# PCB_RX.net
KiCad netlist of a schematic drawn in Altium Designer
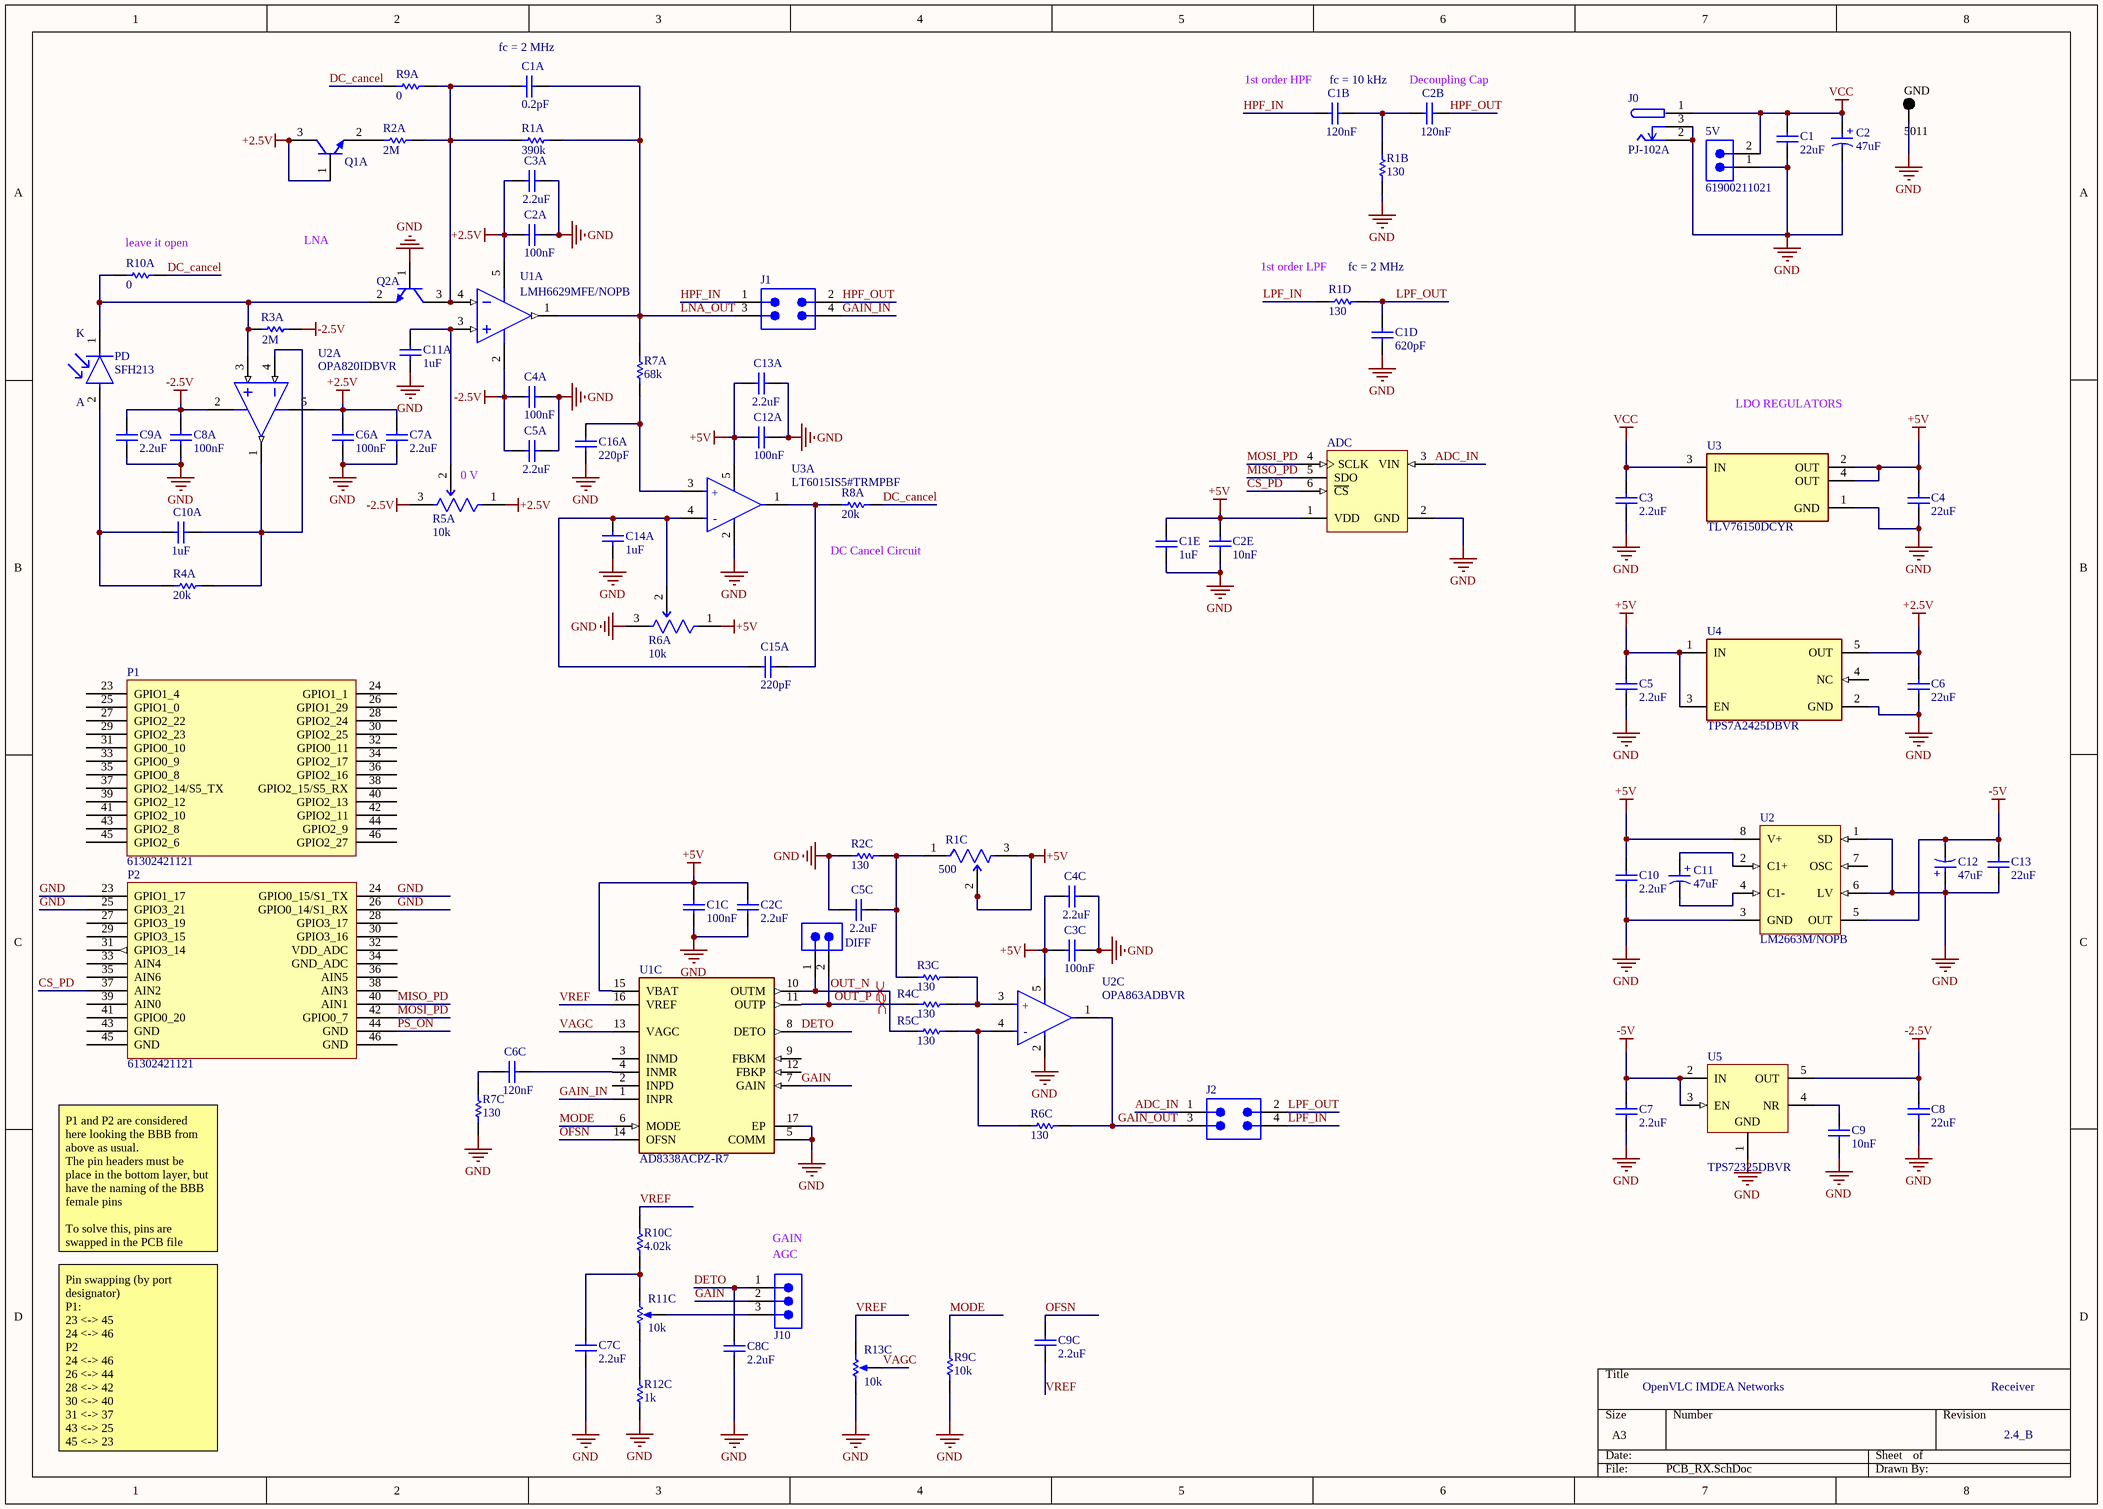
[diagram p0: PCB_RX.SchDoc]

(export (version "E")
  (design (tool "Eeschema 10.0.6"))
  (components
    (comp (ref "5V")
      (value "61900211021")
      (footprint "61900211021")
      (libsource (lib "Altium Content Vault") (part "Header_Male_1R_02P"))
    )
    (comp (ref "ADC")
      (value "ADS7886SBDBVR")
      (footprint "TI-DBV6_M")
      (fields (field (name "MANUFACTURER") "Texas Instruments"))
      (libsource (lib "Altium Content Vault") (part "TI-ADS788XDXX6"))
    )
    (comp (ref "C1")
      (value "22uF")
      (footprint "RESC1608X55N")
      (description "Capacitor")
      (fields (field (name "Comment") "Cap") (field (name "PUBLISHER") "Altium Limited"))
      (libsource (lib "Miscellaneous Devices") (part "Cap"))
    )
    (comp (ref "C1A")
      (value "0.2pF")
      (footprint "RESC1608X55N")
      (description "Capacitor")
      (fields (field (name "Comment") "Cap") (field (name "PUBLISHER") "Altium Limited"))
      (libsource (lib "Miscellaneous Devices") (part "Cap"))
    )
    (comp (ref "C1B")
      (value "120nF")
      (footprint "RESC1608X55N")
      (description "Capacitor")
      (fields (field (name "Comment") "Cap") (field (name "PUBLISHER") "Altium Limited"))
      (libsource (lib "Miscellaneous Devices") (part "Cap"))
    )
    (comp (ref "C1C")
      (value "100nF")
      (footprint "RESC1608X55N")
      (description "Capacitor")
      (fields (field (name "Comment") "Cap") (field (name "PUBLISHER") "Altium Limited"))
      (libsource (lib "Miscellaneous Devices") (part "Cap"))
    )
    (comp (ref "C1D")
      (value "620pF")
      (footprint "RESC1608X55N")
      (description "Capacitor")
      (fields (field (name "Comment") "Cap") (field (name "PUBLISHER") "Altium Limited"))
      (libsource (lib "Miscellaneous Devices") (part "Cap"))
    )
    (comp (ref "C1E")
      (value "1uF")
      (footprint "RESC1608X55N")
      (description "Capacitor")
      (fields (field (name "Comment") "Cap") (field (name "PUBLISHER") "Altium Limited"))
      (libsource (lib "Miscellaneous Devices") (part "Cap"))
    )
    (comp (ref "C2")
      (value "47uF")
      (footprint "WCAP-PSLP_D5H5.5")
      (description "875105242006 WCAP-PSLP Aluminum Polymer Capacitors")
      (fields (field (name "TOLERANCE") "20%"))
      (libsource (lib "Altium Content Vault") (part "Capacitor_Polarized"))
    )
    (comp (ref "C2A")
      (value "100nF")
      (footprint "RESC1608X55N")
      (description "Capacitor")
      (fields (field (name "Comment") "Cap") (field (name "PUBLISHER") "Altium Limited"))
      (libsource (lib "Miscellaneous Devices") (part "Cap"))
    )
    (comp (ref "C2B")
      (value "120nF")
      (footprint "RESC1608X55N")
      (description "Capacitor")
      (fields (field (name "Comment") "Cap") (field (name "PUBLISHER") "Altium Limited"))
      (libsource (lib "Miscellaneous Devices") (part "Cap"))
    )
    (comp (ref "C2C")
      (value "2.2uF")
      (footprint "RESC1608X55N")
      (description "Capacitor")
      (fields (field (name "Comment") "Cap") (field (name "PUBLISHER") "Altium Limited"))
      (libsource (lib "Miscellaneous Devices") (part "Cap"))
    )
    (comp (ref "C2E")
      (value "10nF")
      (footprint "RESC1608X55N")
      (description "Capacitor")
      (fields (field (name "Comment") "Cap") (field (name "PUBLISHER") "Altium Limited"))
      (libsource (lib "Miscellaneous Devices") (part "Cap"))
    )
    (comp (ref "C3")
      (value "2.2uF")
      (footprint "RESC1608X55N")
      (description "Capacitor")
      (fields (field (name "Comment") "Cap") (field (name "PUBLISHER") "Altium Limited"))
      (libsource (lib "Miscellaneous Devices") (part "Cap"))
    )
    (comp (ref "C3A")
      (value "2.2uF")
      (footprint "RESC1608X55N")
      (description "Capacitor")
      (fields (field (name "Comment") "Cap") (field (name "PUBLISHER") "Altium Limited"))
      (libsource (lib "Miscellaneous Devices") (part "Cap"))
    )
    (comp (ref "C3C")
      (value "100nF")
      (footprint "RESC1608X55N")
      (description "Capacitor")
      (fields (field (name "Comment") "Cap") (field (name "PUBLISHER") "Altium Limited"))
      (libsource (lib "Miscellaneous Devices") (part "Cap"))
    )
    (comp (ref "C4")
      (value "22uF")
      (footprint "RESC1608X55N")
      (description "Capacitor")
      (fields (field (name "Comment") "Cap") (field (name "PUBLISHER") "Altium Limited"))
      (libsource (lib "Miscellaneous Devices") (part "Cap"))
    )
    (comp (ref "C4A")
      (value "100nF")
      (footprint "RESC1608X55N")
      (description "Capacitor")
      (fields (field (name "Comment") "Cap") (field (name "PUBLISHER") "Altium Limited"))
      (libsource (lib "Miscellaneous Devices") (part "Cap"))
    )
    (comp (ref "C4C")
      (value "2.2uF")
      (footprint "RESC1608X55N")
      (description "Capacitor")
      (fields (field (name "Comment") "Cap") (field (name "PUBLISHER") "Altium Limited"))
      (libsource (lib "Miscellaneous Devices") (part "Cap"))
    )
    (comp (ref "C5")
      (value "2.2uF")
      (footprint "RESC1608X55N")
      (description "Capacitor")
      (fields (field (name "Comment") "Cap") (field (name "PUBLISHER") "Altium Limited"))
      (libsource (lib "Miscellaneous Devices") (part "Cap"))
    )
    (comp (ref "C5A")
      (value "2.2uF")
      (footprint "RESC1608X55N")
      (description "Capacitor")
      (fields (field (name "Comment") "Cap") (field (name "PUBLISHER") "Altium Limited"))
      (libsource (lib "Miscellaneous Devices") (part "Cap"))
    )
    (comp (ref "C5C")
      (value "2.2uF")
      (footprint "RESC1608X55N")
      (description "Capacitor")
      (fields (field (name "Comment") "Cap") (field (name "PUBLISHER") "Altium Limited"))
      (libsource (lib "Miscellaneous Devices") (part "Cap"))
    )
    (comp (ref "C6")
      (value "22uF")
      (footprint "RESC1608X55N")
      (description "Capacitor")
      (fields (field (name "Comment") "Cap") (field (name "PUBLISHER") "Altium Limited"))
      (libsource (lib "Miscellaneous Devices") (part "Cap"))
    )
    (comp (ref "C6A")
      (value "100nF")
      (footprint "RESC1608X55N")
      (description "Capacitor")
      (fields (field (name "Comment") "Cap") (field (name "PUBLISHER") "Altium Limited"))
      (libsource (lib "Miscellaneous Devices") (part "Cap"))
    )
    (comp (ref "C6C")
      (value "120nF")
      (footprint "RESC1608X55N")
      (description "Capacitor")
      (fields (field (name "Comment") "Cap") (field (name "PUBLISHER") "Altium Limited"))
      (libsource (lib "Miscellaneous Devices") (part "Cap"))
    )
    (comp (ref "C7")
      (value "2.2uF")
      (footprint "RESC1608X55N")
      (description "Capacitor")
      (fields (field (name "Comment") "Cap") (field (name "PUBLISHER") "Altium Limited"))
      (libsource (lib "Miscellaneous Devices") (part "Cap"))
    )
    (comp (ref "C7A")
      (value "2.2uF")
      (footprint "RESC1608X55N")
      (description "Capacitor")
      (fields (field (name "Comment") "Cap") (field (name "PUBLISHER") "Altium Limited"))
      (libsource (lib "Miscellaneous Devices") (part "Cap"))
    )
    (comp (ref "C7C")
      (value "2.2uF")
      (footprint "RESC1608X55N")
      (description "Capacitor")
      (fields (field (name "Comment") "Cap") (field (name "PUBLISHER") "Altium Limited"))
      (libsource (lib "Miscellaneous Devices") (part "Cap"))
    )
    (comp (ref "C8")
      (value "22uF")
      (footprint "RESC1608X55N")
      (description "Capacitor")
      (fields (field (name "Comment") "Cap") (field (name "PUBLISHER") "Altium Limited"))
      (libsource (lib "Miscellaneous Devices") (part "Cap"))
    )
    (comp (ref "C8A")
      (value "100nF")
      (footprint "RESC1608X55N")
      (description "Capacitor")
      (fields (field (name "Comment") "Cap") (field (name "PUBLISHER") "Altium Limited"))
      (libsource (lib "Miscellaneous Devices") (part "Cap"))
    )
    (comp (ref "C8C")
      (value "2.2uF")
      (footprint "RESC1608X55N")
      (description "Capacitor")
      (fields (field (name "Comment") "Cap") (field (name "PUBLISHER") "Altium Limited"))
      (libsource (lib "Miscellaneous Devices") (part "Cap"))
    )
    (comp (ref "C9")
      (value "10nF")
      (footprint "RESC1608X55N")
      (description "Capacitor")
      (fields (field (name "Comment") "Cap") (field (name "PUBLISHER") "Altium Limited"))
      (libsource (lib "Miscellaneous Devices") (part "Cap"))
    )
    (comp (ref "C9A")
      (value "2.2uF")
      (footprint "RESC1608X55N")
      (description "Capacitor")
      (fields (field (name "Comment") "Cap") (field (name "PUBLISHER") "Altium Limited"))
      (libsource (lib "Miscellaneous Devices") (part "Cap"))
    )
    (comp (ref "C9C")
      (value "2.2uF")
      (footprint "RESC1608X55N")
      (description "Capacitor")
      (fields (field (name "Comment") "Cap") (field (name "PUBLISHER") "Altium Limited"))
      (libsource (lib "Miscellaneous Devices") (part "Cap"))
    )
    (comp (ref "C10")
      (value "2.2uF")
      (footprint "RESC1608X55N")
      (description "Capacitor")
      (fields (field (name "Comment") "Cap") (field (name "PUBLISHER") "Altium Limited"))
      (libsource (lib "Miscellaneous Devices") (part "Cap"))
    )
    (comp (ref "C10A")
      (value "1uF")
      (footprint "RESC1608X55N")
      (description "Capacitor")
      (fields (field (name "Comment") "Cap") (field (name "PUBLISHER") "Altium Limited"))
      (libsource (lib "Miscellaneous Devices") (part "Cap"))
    )
    (comp (ref "C11")
      (value "47uF")
      (footprint "WCAP-PSLP_D5H5.5")
      (description "875105242006 WCAP-PSLP Aluminum Polymer Capacitors")
      (fields (field (name "TOLERANCE") "20%"))
      (libsource (lib "Altium Content Vault") (part "Capacitor_Polarized"))
    )
    (comp (ref "C11A")
      (value "1uF")
      (footprint "RESC1608X55N")
      (description "Capacitor")
      (fields (field (name "Comment") "Cap") (field (name "PUBLISHER") "Altium Limited"))
      (libsource (lib "Miscellaneous Devices") (part "Cap"))
    )
    (comp (ref "C12")
      (value "47uF")
      (footprint "WCAP-PSLP_D5H5.5")
      (description "875105242006 WCAP-PSLP Aluminum Polymer Capacitors")
      (fields (field (name "TOLERANCE") "20%"))
      (libsource (lib "Altium Content Vault") (part "Capacitor_Polarized"))
    )
    (comp (ref "C12A")
      (value "100nF")
      (footprint "RESC1608X55N")
      (description "Capacitor")
      (fields (field (name "Comment") "Cap") (field (name "PUBLISHER") "Altium Limited"))
      (libsource (lib "Miscellaneous Devices") (part "Cap"))
    )
    (comp (ref "C13")
      (value "22uF")
      (footprint "RESC1608X55N")
      (description "Capacitor")
      (fields (field (name "Comment") "Cap") (field (name "PUBLISHER") "Altium Limited"))
      (libsource (lib "Miscellaneous Devices") (part "Cap"))
    )
    (comp (ref "C13A")
      (value "2.2uF")
      (footprint "RESC1608X55N")
      (description "Capacitor")
      (fields (field (name "Comment") "Cap") (field (name "PUBLISHER") "Altium Limited"))
      (libsource (lib "Miscellaneous Devices") (part "Cap"))
    )
    (comp (ref "C14A")
      (value "1uF")
      (footprint "RESC1608X55N")
      (description "Capacitor")
      (fields (field (name "Comment") "Cap") (field (name "PUBLISHER") "Altium Limited"))
      (libsource (lib "Miscellaneous Devices") (part "Cap"))
    )
    (comp (ref "C15A")
      (value "220pF")
      (footprint "RESC1608X55N")
      (description "Capacitor")
      (fields (field (name "Comment") "Cap") (field (name "PUBLISHER") "Altium Limited"))
      (libsource (lib "Miscellaneous Devices") (part "Cap"))
    )
    (comp (ref "C16A")
      (value "220pF")
      (footprint "RESC1608X55N")
      (description "Capacitor")
      (fields (field (name "Comment") "Cap") (field (name "PUBLISHER") "Altium Limited"))
      (libsource (lib "Miscellaneous Devices") (part "Cap"))
    )
    (comp (ref "DIFF")
      (value "61300211121")
      (footprint "61300211121")
      (libsource (lib "Altium Content Vault") (part "Header_Male_1R_02P"))
    )
    (comp (ref "GND")
      (value "5011")
      (footprint "KSTN-5011_V")
      (description "Test Point, Black, Through Hole, RoHS, Bulk")
      (fields (field (name "MANUFACTURER") "Keystone"))
      (libsource (lib "Altium Content Vault") (part "TESTPOINT_BLACK"))
    )
    (comp (ref "J0")
      (value "PJ-102A")
      (footprint "FP-PJ-102A-MFG")
      (description "PJ-102A 2.0 x 6.5 mm, 2.5 A, Horizontal, Through Hole, Tapered Pins, Dc Power Jack Connector")
      (libsource (lib "Altium Content Vault") (part "c639f672d24b5d70918fa8d934b95d1"))
    )
    (comp (ref "J1")
      (value "61300421121")
      (footprint "61300421121")
      (libsource (lib "Altium Content Vault") (part "Header_Male_2R_04P"))
    )
    (comp (ref "J2")
      (value "61300421121")
      (footprint "61300421121")
      (libsource (lib "Altium Content Vault") (part "Header_Male_2R_04P"))
    )
    (comp (ref "J10")
      (value "61300311121")
      (footprint "61300311121")
      (libsource (lib "Altium Content Vault") (part "Header_Male_1R_03P"))
    )
    (comp (ref "P1")
      (value "61302421121")
      (footprint "BBB_CAPE_NO_HEADER_R_24")
      (libsource (lib "BeagleBoneCape") (part "BBB_P8_reduced"))
    )
    (comp (ref "P2")
      (value "61302421121")
      (footprint "BBB_CAPE_NO_HEADER_R_24")
      (libsource (lib "BeagleBoneCape") (part "BBB_P9_reduced"))
    )
    (comp (ref "PD")
      (value "SFH213")
      (footprint "FP-SFH213-0")
      (description "SENSOR PHOTODIODE 850NM RADIAL")
      (fields (field (name "MANUFACTURER") "OSRAM") (field (name "VOLTAGE") "50V"))
      (libsource (lib "Altium Content Vault") (part "9b7c99953c265a88c20b8f1023d9605"))
    )
    (comp (ref "Q1A")
      (value "NESG340033")
      (footprint "ONSC-SOT-23-3-318-08_V")
      (description "General Purpose Transistor, NPN Silicon, 3-Pin SOT-23, Pb-Free, Tape and Reel")
      (fields (field (name "PARTNUMBER") "MMBT2222LT1G") (field (name "MANUFACTURER") "On Semiconductor"))
      (libsource (lib "Altium Content Vault") (part "ONSC-NPN-B1E2C3-3"))
    )
    (comp (ref "Q2A")
      (value "NESG340033")
      (footprint "ONSC-SOT-23-3-318-08_V")
      (description "General Purpose Transistor, NPN Silicon, 3-Pin SOT-23, Pb-Free, Tape and Reel")
      (fields (field (name "PARTNUMBER") "MMBT2222LT1G") (field (name "MANUFACTURER") "On Semiconductor"))
      (libsource (lib "Altium Content Vault") (part "ONSC-NPN-B1E2C3-3"))
    )
    (comp (ref "R1A")
      (value "390k")
      (footprint "RESC1608X55N")
      (description "Resistor")
      (fields (field (name "Comment") "Res1") (field (name "PUBLISHER") "Altium Limited"))
      (libsource (lib "Miscellaneous Devices") (part "Res1"))
    )
    (comp (ref "R1B")
      (value "130")
      (footprint "RESC1608X55N")
      (description "Resistor")
      (fields (field (name "Comment") "Res1") (field (name "PUBLISHER") "Altium Limited"))
      (libsource (lib "Miscellaneous Devices") (part "Res1"))
    )
    (comp (ref "R1C")
      (value "500")
      (footprint "FP-3296W-MFG")
      (description "TRIMMER 10K OHM 0.5W PC PIN TOP")
      (fields (field (name "TOLERANCE") "10%"))
      (libsource (lib "Altium Content Vault") (part "2dcfd2547301a7d3209a5e99acfd772"))
    )
    (comp (ref "R1D")
      (value "130")
      (footprint "RESC1608X55N")
      (description "Resistor")
      (fields (field (name "Comment") "Res1") (field (name "PUBLISHER") "Altium Limited"))
      (libsource (lib "Miscellaneous Devices") (part "Res1"))
    )
    (comp (ref "R2A")
      (value "2M")
      (footprint "RESC1608X55N")
      (description "Resistor")
      (fields (field (name "Comment") "Res1") (field (name "PUBLISHER") "Altium Limited"))
      (libsource (lib "Miscellaneous Devices") (part "Res1"))
    )
    (comp (ref "R2C")
      (value "130")
      (footprint "RESC1608X55N")
      (description "Resistor")
      (fields (field (name "Comment") "Res1") (field (name "PUBLISHER") "Altium Limited"))
      (libsource (lib "Miscellaneous Devices") (part "Res1"))
    )
    (comp (ref "R3A")
      (value "2M")
      (footprint "RESC1608X55N")
      (description "Resistor")
      (fields (field (name "Comment") "Res1") (field (name "PUBLISHER") "Altium Limited"))
      (libsource (lib "Miscellaneous Devices") (part "Res1"))
    )
    (comp (ref "R3C")
      (value "130")
      (footprint "RESC1608X55N")
      (description "Resistor")
      (fields (field (name "Comment") "Res1") (field (name "PUBLISHER") "Altium Limited"))
      (libsource (lib "Miscellaneous Devices") (part "Res1"))
    )
    (comp (ref "R4A")
      (value "20k")
      (footprint "RESC1608X55N")
      (description "Resistor")
      (fields (field (name "Comment") "Res1") (field (name "PUBLISHER") "Altium Limited"))
      (libsource (lib "Miscellaneous Devices") (part "Res1"))
    )
    (comp (ref "R4C")
      (value "130")
      (footprint "RESC1608X55N")
      (description "Resistor")
      (fields (field (name "Comment") "Res1") (field (name "PUBLISHER") "Altium Limited"))
      (libsource (lib "Miscellaneous Devices") (part "Res1"))
    )
    (comp (ref "R5A")
      (value "10k")
      (footprint "FP-3296W-MFG")
      (description "TRIMMER 10K OHM 0.5W PC PIN TOP")
      (fields (field (name "TOLERANCE") "10%"))
      (libsource (lib "Altium Content Vault") (part "2dcfd2547301a7d3209a5e99acfd772"))
    )
    (comp (ref "R5C")
      (value "130")
      (footprint "RESC1608X55N")
      (description "Resistor")
      (fields (field (name "Comment") "Res1") (field (name "PUBLISHER") "Altium Limited"))
      (libsource (lib "Miscellaneous Devices") (part "Res1"))
    )
    (comp (ref "R6A")
      (value "10k")
      (footprint "FP-3296W-MFG")
      (description "TRIMMER 10K OHM 0.5W PC PIN TOP")
      (fields (field (name "TOLERANCE") "10%"))
      (libsource (lib "Altium Content Vault") (part "2dcfd2547301a7d3209a5e99acfd772"))
    )
    (comp (ref "R6C")
      (value "130")
      (footprint "RESC1608X55N")
      (description "Resistor")
      (fields (field (name "Comment") "Res1") (field (name "PUBLISHER") "Altium Limited"))
      (libsource (lib "Miscellaneous Devices") (part "Res1"))
    )
    (comp (ref "R7A")
      (value "68k")
      (footprint "RESC1608X55N")
      (description "Resistor")
      (fields (field (name "Comment") "Res1") (field (name "PUBLISHER") "Altium Limited"))
      (libsource (lib "Miscellaneous Devices") (part "Res1"))
    )
    (comp (ref "R7C")
      (value "130")
      (footprint "RESC1608X55N")
      (description "Resistor")
      (fields (field (name "Comment") "Res1") (field (name "PUBLISHER") "Altium Limited"))
      (libsource (lib "Miscellaneous Devices") (part "Res1"))
    )
    (comp (ref "R8A")
      (value "20k")
      (footprint "RESC1608X55N")
      (description "Resistor")
      (fields (field (name "Comment") "Res1") (field (name "PUBLISHER") "Altium Limited"))
      (libsource (lib "Miscellaneous Devices") (part "Res1"))
    )
    (comp (ref "R9A")
      (value "0")
      (footprint "RESC1608X55N")
      (description "Resistor")
      (fields (field (name "Comment") "Res1") (field (name "PUBLISHER") "Altium Limited"))
      (libsource (lib "Miscellaneous Devices") (part "Res1"))
    )
    (comp (ref "R9C")
      (value "10k")
      (footprint "RESC1608X55N")
      (description "Resistor")
      (fields (field (name "Comment") "Res1") (field (name "PUBLISHER") "Altium Limited"))
      (libsource (lib "Miscellaneous Devices") (part "Res1"))
    )
    (comp (ref "R10A")
      (value "0")
      (footprint "RESC1608X55N")
      (description "Resistor")
      (fields (field (name "Comment") "Res1") (field (name "PUBLISHER") "Altium Limited"))
      (libsource (lib "Miscellaneous Devices") (part "Res1"))
    )
    (comp (ref "R10C")
      (value "4.02k")
      (footprint "RESC1608X55N")
      (description "Resistor")
      (fields (field (name "Comment") "Res1") (field (name "PUBLISHER") "Altium Limited"))
      (libsource (lib "Miscellaneous Devices") (part "Res1"))
    )
    (comp (ref "R11C")
      (value "10k")
      (footprint "BOUR-3362P")
      (description "Square Trimpot(R) Trimming Potentiometer, 10 KOhm, 300 V, -55 to 125 degC, 3-Pin THD, RoHS, Tube")
      (fields (field (name "TOLERANCE") "1%"))
      (libsource (lib "Altium Content Vault") (part "RES-POT-3"))
    )
    (comp (ref "R12C")
      (value "1k")
      (footprint "RESC1608X55N")
      (description "Resistor")
      (fields (field (name "Comment") "Res1") (field (name "PUBLISHER") "Altium Limited"))
      (libsource (lib "Miscellaneous Devices") (part "Res1"))
    )
    (comp (ref "R13C")
      (value "10k")
      (footprint "BOUR-3362P")
      (description "Square Trimpot(R) Trimming Potentiometer, 10 KOhm, 300 V, -55 to 125 degC, 3-Pin THD, RoHS, Tube")
      (fields (field (name "TOLERANCE") "1%"))
      (libsource (lib "Altium Content Vault") (part "RES-POT-3"))
    )
    (comp (ref "U1A")
      (value "LMH6629MFE/NOPB")
      (footprint "DBV0005A_L")
      (description "Ultra-Low Noise, High-Speed Operational Amplifier with Shutdown, 5-pin SOT-23, 250 Reel")
      (fields (field (name "MANUFACTURER") "Texas Instruments"))
      (libsource (lib "Altium Content Vault") (part "AMP-OPA-LMH6629-5"))
    )
    (comp (ref "U1C")
      (value "AD8338ACPZ-R7")
      (footprint "FP-CP-16-22-IPC_C")
      (description "IC OPAMP VGA 1 CIRCUIT 16LFCSP")
      (fields
        (field (name "OCTOPART") "https://octopart.com/ad8338acpz-r7-analog+devices-21054770")
        (field (name "MANUFACTURER") "Analog Devices")
      )
      (libsource (lib "Altium Content Vault") (part "4ce7887af0b7713ffabab50ab6d8fb3"))
    )
    (comp (ref "U2")
      (value "LM2663M/NOPB")
      (footprint "D0008A_N")
      (description "Switched Capacitor Voltage Converter, 8-pin Narrow SOIC, Pb-Free")
      (fields (field (name "MANUFACTURER") "Texas Instruments"))
      (libsource (lib "Altium Content Vault") (part "PM-CHP-LM2661M-8"))
    )
    (comp (ref "U2A")
      (value "OPA820IDBVR")
      (footprint "DBV0005A_N")
      (fields (field (name "MANUFACTURER") "Texas Instruments"))
      (libsource (lib "Altium Content Vault") (part "TI-AMP-S3-2-DBV5_A"))
    )
    (comp (ref "U2C")
      (value "OPA863ADBVR")
      (footprint "FP-DBV0005A-MFG")
      (libsource (lib "Altium Content Vault") (part "4cd2dec86d87e6d90761bbce91e6ba3"))
    )
    (comp (ref "U3")
      (value "TLV76150DCYR")
      (footprint "FP-DCY0004A-MFG")
      (description "TLV76150DCYR 1-A 16-V high-PSRR linear voltage regulator 4-SOT-223 -40 to 125")
      (libsource (lib "Altium Content Vault") (part "991ffb903c51cf6179ce9942c0606aa"))
    )
    (comp (ref "U3A")
      (value "LT6015IS5#TRMPBF")
      (footprint "FP-S5-5-05-08-1635-MFG")
      (description "IC OPAMP GP 1 CIRCUIT TSOT23-5")
      (fields
        (field (name "MANUFACTURER PART NUMBER") "LT6015MPS5#TRMPBF")
        (field (name "OCTOPART") "https://octopart.com/lt6015mps5%23trmpbf-analog+devices-88316455")
      )
      (libsource (lib "Altium Content Vault") (part "1dcd28e651784f0a5a8ed6f8452eeff"))
    )
    (comp (ref "U4")
      (value "TPS7A2425DBVR")
      (footprint "FP-DBV0005A-MFG")
      (libsource (lib "Altium Content Vault") (part "a4c7da49f906937765e1f9127586bb8"))
    )
    (comp (ref "U5")
      (value "TPS72325DBVR")
      (footprint "DBV0005A_N")
      (fields (field (name "MANUFACTURER") "Texas Instruments"))
      (libsource (lib "Altium Content Vault") (part "TI-TPS72325-DBV5"))
    )
  )
  (nets
    (net (code "1") (name "+2.5V") (class "Default")
      (node (ref "C2A") (pin "1") (pinfunction "1_1") (pintype "passive"))
      (node (ref "C3A") (pin "1") (pinfunction "1_1") (pintype "passive"))
      (node (ref "C6") (pin "2") (pinfunction "2_2") (pintype "passive"))
      (node (ref "C6A") (pin "1") (pinfunction "1_1") (pintype "passive"))
      (node (ref "C7A") (pin "1") (pinfunction "1_1") (pintype "passive"))
      (node (ref "Q1A") (pin "1") (pinfunction "B_1") (pintype "passive"))
      (node (ref "Q1A") (pin "3") (pinfunction "C_3") (pintype "passive"))
      (node (ref "R5A") (pin "1") (pinfunction "CCW_1") (pintype "passive"))
      (node (ref "U1A") (pin "5") (pinfunction "V+_5") (pintype "power_in"))
      (node (ref "U2A") (pin "5") (pinfunction "VS+_5") (pintype "power_in"))
      (node (ref "U4") (pin "5") (pinfunction "OUT_5") (pintype "passive"))
    )
    (net (code "2") (name "+5V") (class "Default")
      (node (ref "ADC") (pin "1") (pinfunction "VDD_1") (pintype "power_in"))
      (node (ref "C10") (pin "2") (pinfunction "2_2") (pintype "passive"))
      (node (ref "C12A") (pin "1") (pinfunction "1_1") (pintype "passive"))
      (node (ref "C13A") (pin "1") (pinfunction "1_1") (pintype "passive"))
      (node (ref "C1C") (pin "1") (pinfunction "1_1") (pintype "passive"))
      (node (ref "C1E") (pin "1") (pinfunction "1_1") (pintype "passive"))
      (node (ref "C2C") (pin "1") (pinfunction "1_1") (pintype "passive"))
      (node (ref "C2E") (pin "1") (pinfunction "1_1") (pintype "passive"))
      (node (ref "C3C") (pin "1") (pinfunction "1_1") (pintype "passive"))
      (node (ref "C4") (pin "2") (pinfunction "2_2") (pintype "passive"))
      (node (ref "C4C") (pin "1") (pinfunction "1_1") (pintype "passive"))
      (node (ref "C5") (pin "2") (pinfunction "2_2") (pintype "passive"))
      (node (ref "R1C") (pin "2") (pinfunction "WIPER_2") (pintype "passive"))
      (node (ref "R1C") (pin "3") (pinfunction "CW_3") (pintype "passive"))
      (node (ref "R6A") (pin "1") (pinfunction "CCW_1") (pintype "passive"))
      (node (ref "U1C") (pin "15") (pinfunction "VBAT_15") (pintype "power_in"))
      (node (ref "U2") (pin "8") (pinfunction "V+_8") (pintype "power_in"))
      (node (ref "U2C") (pin "5") (pinfunction "VS+_5") (pintype "power_in"))
      (node (ref "U3") (pin "2") (pinfunction "OUT_2") (pintype "passive"))
      (node (ref "U3") (pin "4") (pinfunction "OUT_4") (pintype "passive"))
      (node (ref "U3A") (pin "5") (pinfunction "V+_5") (pintype "power_in"))
      (node (ref "U4") (pin "1") (pinfunction "IN_1") (pintype "passive"))
      (node (ref "U4") (pin "3") (pinfunction "EN_3") (pintype "power_in"))
    )
    (net (code "3") (name "-2.5V") (class "Default")
      (node (ref "C4A") (pin "1") (pinfunction "1_1") (pintype "passive"))
      (node (ref "C5A") (pin "1") (pinfunction "1_1") (pintype "passive"))
      (node (ref "C8") (pin "2") (pinfunction "2_2") (pintype "passive"))
      (node (ref "C8A") (pin "1") (pinfunction "1_1") (pintype "passive"))
      (node (ref "C9A") (pin "1") (pinfunction "1_1") (pintype "passive"))
      (node (ref "R3A") (pin "1") (pinfunction "1_1") (pintype "passive"))
      (node (ref "R5A") (pin "3") (pinfunction "CW_3") (pintype "passive"))
      (node (ref "U1A") (pin "2") (pinfunction "V-_2") (pintype "power_in"))
      (node (ref "U2A") (pin "2") (pinfunction "VS-_2") (pintype "power_in"))
      (node (ref "U5") (pin "5") (pinfunction "OUT_5") (pintype "power_in"))
    )
    (net (code "4") (name "-5V") (class "Default")
      (node (ref "C12") (pin "2") (pinfunction "N_2") (pintype "passive"))
      (node (ref "C13") (pin "2") (pinfunction "2_2") (pintype "passive"))
      (node (ref "C7") (pin "2") (pinfunction "2_2") (pintype "passive"))
      (node (ref "U2") (pin "5") (pinfunction "OUT_5") (pintype "power_in"))
      (node (ref "U5") (pin "2") (pinfunction "IN_2") (pintype "power_in"))
      (node (ref "U5") (pin "3") (pinfunction "EN_3") (pintype "input"))
    )
    (net (code "5") (name "/ADC_IN") (class "Default")
      (node (ref "ADC") (pin "3") (pinfunction "VIN_3") (pintype "input"))
      (node (ref "J2") (pin "1") (pinfunction "1_1") (pintype "passive"))
    )
    (net (code "6") (name "/CS_PD") (class "Default")
      (node (ref "ADC") (pin "6") (pinfunction "~{CS}_6") (pintype "input"))
      (node (ref "P2") (pin "37") (pinfunction "AIN2_37") (pintype "passive"))
    )
    (net (code "7") (name "/DC_cancel") (class "Default")
      (node (ref "R10A") (pin "1") (pinfunction "1_1") (pintype "passive"))
      (node (ref "R8A") (pin "1") (pinfunction "1_1") (pintype "passive"))
      (node (ref "R9A") (pin "2") (pinfunction "2_2") (pintype "passive"))
    )
    (net (code "8") (name "/DETO") (class "Default")
      (node (ref "C8C") (pin "2") (pinfunction "2_2") (pintype "passive"))
      (node (ref "J10") (pin "1") (pinfunction "1_1") (pintype "passive"))
      (node (ref "U1C") (pin "8") (pinfunction "DETO_8") (pintype "output"))
    )
    (net (code "9") (name "/GAIN") (class "Default")
      (node (ref "J10") (pin "2") (pinfunction "2_2") (pintype "passive"))
      (node (ref "U1C") (pin "7") (pinfunction "GAIN_7") (pintype "input"))
    )
    (net (code "10") (name "/GAIN_IN") (class "Default")
      (node (ref "J1") (pin "4") (pinfunction "4_4") (pintype "passive"))
      (node (ref "U1C") (pin "1") (pinfunction "INPR_1") (pintype "passive"))
    )
    (net (code "11") (name "/GAIN_OUT") (class "Default")
      (node (ref "J2") (pin "3") (pinfunction "3_3") (pintype "passive"))
      (node (ref "R6C") (pin "1") (pinfunction "1_1") (pintype "passive"))
      (node (ref "U2C") (pin "1") (pinfunction "VOUT_1") (pintype "passive"))
    )
    (net (code "12") (name "/HPF_IN") (class "Default")
      (node (ref "C1B") (pin "1") (pinfunction "1_1") (pintype "passive"))
      (node (ref "J1") (pin "1") (pinfunction "1_1") (pintype "passive"))
    )
    (net (code "13") (name "/HPF_OUT") (class "Default")
      (node (ref "C2B") (pin "2") (pinfunction "2_2") (pintype "passive"))
      (node (ref "J1") (pin "2") (pinfunction "2_2") (pintype "passive"))
    )
    (net (code "14") (name "/LNA_OUT") (class "Default")
      (node (ref "C1A") (pin "2") (pinfunction "2_2") (pintype "passive"))
      (node (ref "J1") (pin "3") (pinfunction "3_3") (pintype "passive"))
      (node (ref "R1A") (pin "1") (pinfunction "1_1") (pintype "passive"))
      (node (ref "R7A") (pin "1") (pinfunction "1_1") (pintype "passive"))
      (node (ref "U1A") (pin "1") (pinfunction "OUT_1") (pintype "output"))
    )
    (net (code "15") (name "/LPF_IN") (class "Default")
      (node (ref "J2") (pin "4") (pinfunction "4_4") (pintype "passive"))
      (node (ref "R1D") (pin "2") (pinfunction "2_2") (pintype "passive"))
    )
    (net (code "16") (name "/LPF_OUT") (class "Default")
      (node (ref "C1D") (pin "1") (pinfunction "1_1") (pintype "passive"))
      (node (ref "J2") (pin "2") (pinfunction "2_2") (pintype "passive"))
      (node (ref "R1D") (pin "1") (pinfunction "1_1") (pintype "passive"))
    )
    (net (code "17") (name "/MISO_PD") (class "Default")
      (node (ref "ADC") (pin "5") (pinfunction "SDO_5") (pintype "tri_state"))
      (node (ref "P2") (pin "40") (pinfunction "AIN1_40") (pintype "passive"))
    )
    (net (code "18") (name "/MODE") (class "Default")
      (node (ref "R9C") (pin "2") (pinfunction "2_2") (pintype "passive"))
      (node (ref "U1C") (pin "6") (pinfunction "MODE_6") (pintype "input"))
    )
    (net (code "19") (name "/MOSI_PD") (class "Default")
      (node (ref "ADC") (pin "4") (pinfunction "SCLK_4") (pintype "input"))
      (node (ref "P2") (pin "42") (pinfunction "GPIO0_7_42") (pintype "passive"))
    )
    (net (code "20") (name "/OFSN") (class "Default")
      (node (ref "C9C") (pin "2") (pinfunction "2_2") (pintype "passive"))
      (node (ref "U1C") (pin "14") (pinfunction "OFSN_14") (pintype "passive"))
    )
    (net (code "21") (name "/OUT_N") (class "Default")
      (node (ref "DIFF") (pin "1") (pinfunction "1_1") (pintype "passive"))
      (node (ref "R5C") (pin "2") (pinfunction "2_2") (pintype "passive"))
      (node (ref "U1C") (pin "10") (pinfunction "OUTM_10") (pintype "output"))
    )
    (net (code "22") (name "/OUT_P") (class "Default")
      (node (ref "DIFF") (pin "2") (pinfunction "2_2") (pintype "passive"))
      (node (ref "R4C") (pin "2") (pinfunction "2_2") (pintype "passive"))
      (node (ref "U1C") (pin "11") (pinfunction "OUTP_11") (pintype "output"))
    )
    (net (code "23") (name "/PS_ON") (class "Default")
      (node (ref "P2") (pin "44") (pinfunction "GND_44") (pintype "passive"))
    )
    (net (code "24") (name "/VAGC") (class "Default")
      (node (ref "R13C") (pin "2") (pinfunction "S_2") (pintype "passive"))
      (node (ref "U1C") (pin "13") (pinfunction "VAGC_13") (pintype "power_in"))
    )
    (net (code "25") (name "/VREF") (class "Default")
      (node (ref "C9C") (pin "1") (pinfunction "1_1") (pintype "passive"))
      (node (ref "R10C") (pin "1") (pinfunction "1_1") (pintype "passive"))
      (node (ref "R13C") (pin "3") (pinfunction "CW_3") (pintype "passive"))
      (node (ref "U1C") (pin "16") (pinfunction "VREF_16") (pintype "power_in"))
    )
    (net (code "26") (name "GND") (class "Default")
      (node (ref "5V") (pin "1") (pinfunction "1_1") (pintype "passive"))
      (node (ref "ADC") (pin "2") (pinfunction "GND_2") (pintype "power_in"))
      (node (ref "C1") (pin "2") (pinfunction "2_2") (pintype "passive"))
      (node (ref "C10") (pin "1") (pinfunction "1_1") (pintype "passive"))
      (node (ref "C11A") (pin "1") (pinfunction "1_1") (pintype "passive"))
      (node (ref "C12") (pin "1") (pinfunction "P_1") (pintype "passive"))
      (node (ref "C12A") (pin "2") (pinfunction "2_2") (pintype "passive"))
      (node (ref "C13") (pin "1") (pinfunction "1_1") (pintype "passive"))
      (node (ref "C13A") (pin "2") (pinfunction "2_2") (pintype "passive"))
      (node (ref "C14A") (pin "1") (pinfunction "1_1") (pintype "passive"))
      (node (ref "C16A") (pin "2") (pinfunction "2_2") (pintype "passive"))
      (node (ref "C1C") (pin "2") (pinfunction "2_2") (pintype "passive"))
      (node (ref "C1D") (pin "2") (pinfunction "2_2") (pintype "passive"))
      (node (ref "C1E") (pin "2") (pinfunction "2_2") (pintype "passive"))
      (node (ref "C2") (pin "2") (pinfunction "N_2") (pintype "passive"))
      (node (ref "C2A") (pin "2") (pinfunction "2_2") (pintype "passive"))
      (node (ref "C2C") (pin "2") (pinfunction "2_2") (pintype "passive"))
      (node (ref "C2E") (pin "2") (pinfunction "2_2") (pintype "passive"))
      (node (ref "C3") (pin "1") (pinfunction "1_1") (pintype "passive"))
      (node (ref "C3A") (pin "2") (pinfunction "2_2") (pintype "passive"))
      (node (ref "C3C") (pin "2") (pinfunction "2_2") (pintype "passive"))
      (node (ref "C4") (pin "1") (pinfunction "1_1") (pintype "passive"))
      (node (ref "C4A") (pin "2") (pinfunction "2_2") (pintype "passive"))
      (node (ref "C4C") (pin "2") (pinfunction "2_2") (pintype "passive"))
      (node (ref "C5") (pin "1") (pinfunction "1_1") (pintype "passive"))
      (node (ref "C5A") (pin "2") (pinfunction "2_2") (pintype "passive"))
      (node (ref "C5C") (pin "1") (pinfunction "1_1") (pintype "passive"))
      (node (ref "C6") (pin "1") (pinfunction "1_1") (pintype "passive"))
      (node (ref "C6A") (pin "2") (pinfunction "2_2") (pintype "passive"))
      (node (ref "C7") (pin "1") (pinfunction "1_1") (pintype "passive"))
      (node (ref "C7A") (pin "2") (pinfunction "2_2") (pintype "passive"))
      (node (ref "C7C") (pin "1") (pinfunction "1_1") (pintype "passive"))
      (node (ref "C8") (pin "1") (pinfunction "1_1") (pintype "passive"))
      (node (ref "C8A") (pin "2") (pinfunction "2_2") (pintype "passive"))
      (node (ref "C8C") (pin "1") (pinfunction "1_1") (pintype "passive"))
      (node (ref "C9") (pin "1") (pinfunction "1_1") (pintype "passive"))
      (node (ref "C9A") (pin "2") (pinfunction "2_2") (pintype "passive"))
      (node (ref "GND") (pin "1") (pinfunction "1_1") (pintype "passive"))
      (node (ref "J0") (pin "2") (pinfunction "2_2") (pintype "passive"))
      (node (ref "J0") (pin "3") (pinfunction "3_3") (pintype "passive"))
      (node (ref "P2") (pin "23") (pinfunction "GPIO1_17_23") (pintype "passive"))
      (node (ref "P2") (pin "24") (pinfunction "GPIO0_15/S1_TX_24") (pintype "passive"))
      (node (ref "P2") (pin "25") (pinfunction "GPIO3_21_25") (pintype "passive"))
      (node (ref "P2") (pin "26") (pinfunction "GPIO0_14/S1_RX_26") (pintype "passive"))
      (node (ref "Q2A") (pin "1") (pinfunction "B_1") (pintype "passive"))
      (node (ref "R12C") (pin "1") (pinfunction "1_1") (pintype "passive"))
      (node (ref "R13C") (pin "1") (pinfunction "CCW_1") (pintype "passive"))
      (node (ref "R1B") (pin "2") (pinfunction "2_2") (pintype "passive"))
      (node (ref "R2C") (pin "2") (pinfunction "2_2") (pintype "passive"))
      (node (ref "R6A") (pin "3") (pinfunction "CW_3") (pintype "passive"))
      (node (ref "R7C") (pin "2") (pinfunction "2_2") (pintype "passive"))
      (node (ref "R9C") (pin "1") (pinfunction "1_1") (pintype "passive"))
      (node (ref "U1C") (pin "17") (pinfunction "EP_17") (pintype "power_in"))
      (node (ref "U1C") (pin "5") (pinfunction "COMM_5") (pintype "power_in"))
      (node (ref "U2") (pin "1") (pinfunction "SD_1") (pintype "input"))
      (node (ref "U2") (pin "3") (pinfunction "GND_3") (pintype "power_in"))
      (node (ref "U2") (pin "6") (pinfunction "LV_6") (pintype "input"))
      (node (ref "U2C") (pin "2") (pinfunction "VS-_2") (pintype "power_in"))
      (node (ref "U3") (pin "1") (pinfunction "GND_1") (pintype "power_in"))
      (node (ref "U3A") (pin "2") (pinfunction "V-_2") (pintype "power_in"))
      (node (ref "U4") (pin "2") (pinfunction "GND_2") (pintype "power_in"))
      (node (ref "U5") (pin "1") (pinfunction "GND_1") (pintype "power_in"))
    )
    (net (code "27") (name "Net-(C1B-Pad2)") (class "Default")
      (node (ref "C1B") (pin "2") (pinfunction "2_2") (pintype "passive"))
      (node (ref "C2B") (pin "1") (pinfunction "1_1") (pintype "passive"))
      (node (ref "R1B") (pin "1") (pinfunction "1_1") (pintype "passive"))
    )
    (net (code "28") (name "Net-(C6C-Pad1)") (class "Default")
      (node (ref "C6C") (pin "1") (pinfunction "1_1") (pintype "passive"))
      (node (ref "R7C") (pin "1") (pinfunction "1_1") (pintype "passive"))
    )
    (net (code "29") (name "Net-(C11-N)") (class "Default")
      (node (ref "C11") (pin "2") (pinfunction "N_2") (pintype "passive"))
      (node (ref "U2") (pin "4") (pinfunction "C1-_4") (pintype "input"))
    )
    (net (code "30") (name "Net-(C11-P)") (class "Default")
      (node (ref "C11") (pin "1") (pinfunction "P_1") (pintype "passive"))
      (node (ref "U2") (pin "2") (pinfunction "C1+_2") (pintype "input"))
    )
    (net (code "31") (name "Net-(PD-A)") (class "Default")
      (node (ref "C10A") (pin "1") (pinfunction "1_1") (pintype "passive"))
      (node (ref "PD") (pin "2") (pinfunction "A_2") (pintype "passive"))
      (node (ref "R4A") (pin "2") (pinfunction "2_2") (pintype "passive"))
    )
    (net (code "32") (name "Net-(PD-C)") (class "Default")
      (node (ref "PD") (pin "1") (pinfunction "C_1") (pintype "passive"))
      (node (ref "Q2A") (pin "2") (pinfunction "E_2") (pintype "passive"))
      (node (ref "R10A") (pin "2") (pinfunction "2_2") (pintype "passive"))
      (node (ref "R3A") (pin "2") (pinfunction "2_2") (pintype "passive"))
      (node (ref "U2A") (pin "3") (pinfunction "IN+_3") (pintype "input"))
    )
    (net (code "33") (name "Net-(Q1A-E)") (class "Default")
      (node (ref "Q1A") (pin "2") (pinfunction "E_2") (pintype "passive"))
      (node (ref "R2A") (pin "2") (pinfunction "2_2") (pintype "passive"))
    )
    (net (code "34") (name "Net-(Q2A-C)") (class "Default")
      (node (ref "C1A") (pin "1") (pinfunction "1_1") (pintype "passive"))
      (node (ref "Q2A") (pin "3") (pinfunction "C_3") (pintype "passive"))
      (node (ref "R1A") (pin "2") (pinfunction "2_2") (pintype "passive"))
      (node (ref "R2A") (pin "1") (pinfunction "1_1") (pintype "passive"))
      (node (ref "R9A") (pin "1") (pinfunction "1_1") (pintype "passive"))
      (node (ref "U1A") (pin "4") (pinfunction "IN-_4") (pintype "input"))
    )
    (net (code "35") (name "Net-(R1C-CCW)") (class "Default")
      (node (ref "C5C") (pin "2") (pinfunction "2_2") (pintype "passive"))
      (node (ref "R1C") (pin "1") (pinfunction "CCW_1") (pintype "passive"))
      (node (ref "R2C") (pin "1") (pinfunction "1_1") (pintype "passive"))
      (node (ref "R3C") (pin "2") (pinfunction "2_2") (pintype "passive"))
    )
    (net (code "36") (name "Net-(R5A-WIPER)") (class "Default")
      (node (ref "C11A") (pin "2") (pinfunction "2_2") (pintype "passive"))
      (node (ref "R5A") (pin "2") (pinfunction "WIPER_2") (pintype "passive"))
      (node (ref "U1A") (pin "3") (pinfunction "IN+_3") (pintype "input"))
    )
    (net (code "37") (name "Net-(R6A-WIPER)") (class "Default")
      (node (ref "C14A") (pin "2") (pinfunction "2_2") (pintype "passive"))
      (node (ref "C15A") (pin "2") (pinfunction "2_2") (pintype "passive"))
      (node (ref "R6A") (pin "2") (pinfunction "WIPER_2") (pintype "passive"))
      (node (ref "U3A") (pin "4") (pinfunction "-IN_4") (pintype "tri_state"))
    )
    (net (code "38") (name "Net-(R11C-CCW)") (class "Default")
      (node (ref "R11C") (pin "1") (pinfunction "CCW_1") (pintype "passive"))
      (node (ref "R12C") (pin "2") (pinfunction "2_2") (pintype "passive"))
    )
    (net (code "39") (name "Net-(R11C-CW)") (class "Default")
      (node (ref "C7C") (pin "2") (pinfunction "2_2") (pintype "passive"))
      (node (ref "R10C") (pin "2") (pinfunction "2_2") (pintype "passive"))
      (node (ref "R11C") (pin "3") (pinfunction "CW_3") (pintype "passive"))
    )
    (net (code "40") (name "Net-(R11C-S)") (class "Default")
      (node (ref "J10") (pin "3") (pinfunction "3_3") (pintype "passive"))
      (node (ref "R11C") (pin "2") (pinfunction "S_2") (pintype "passive"))
    )
    (net (code "41") (name "Net-(U1C-INMR)") (class "Default")
      (node (ref "C6C") (pin "2") (pinfunction "2_2") (pintype "passive"))
      (node (ref "U1C") (pin "4") (pinfunction "INMR_4") (pintype "passive"))
    )
    (net (code "42") (name "Net-(U2A-IN-)") (class "Default")
      (node (ref "C10A") (pin "2") (pinfunction "2_2") (pintype "passive"))
      (node (ref "R4A") (pin "1") (pinfunction "1_1") (pintype "passive"))
      (node (ref "U2A") (pin "1") (pinfunction "OUT_1") (pintype "output"))
      (node (ref "U2A") (pin "4") (pinfunction "IN-_4") (pintype "input"))
    )
    (net (code "43") (name "Net-(U2C-VIN+)") (class "Default")
      (node (ref "R3C") (pin "1") (pinfunction "1_1") (pintype "passive"))
      (node (ref "R4C") (pin "1") (pinfunction "1_1") (pintype "passive"))
      (node (ref "U2C") (pin "3") (pinfunction "VIN+_3") (pintype "tri_state"))
    )
    (net (code "44") (name "Net-(U2C-VIN-)") (class "Default")
      (node (ref "R5C") (pin "1") (pinfunction "1_1") (pintype "passive"))
      (node (ref "R6C") (pin "2") (pinfunction "2_2") (pintype "passive"))
      (node (ref "U2C") (pin "4") (pinfunction "VIN-_4") (pintype "tri_state"))
    )
    (net (code "45") (name "Net-(U3A-+IN)") (class "Default")
      (node (ref "C16A") (pin "1") (pinfunction "1_1") (pintype "passive"))
      (node (ref "R7A") (pin "2") (pinfunction "2_2") (pintype "passive"))
      (node (ref "U3A") (pin "3") (pinfunction "+IN_3") (pintype "tri_state"))
    )
    (net (code "46") (name "Net-(U3A-OUT)") (class "Default")
      (node (ref "C15A") (pin "1") (pinfunction "1_1") (pintype "passive"))
      (node (ref "R8A") (pin "2") (pinfunction "2_2") (pintype "passive"))
      (node (ref "U3A") (pin "1") (pinfunction "OUT_1") (pintype "passive"))
    )
    (net (code "47") (name "Net-(U5-NR)") (class "Default")
      (node (ref "C9") (pin "2") (pinfunction "2_2") (pintype "passive"))
      (node (ref "U5") (pin "4") (pinfunction "NR_4") (pintype "passive"))
    )
    (net (code "48") (name "VCC") (class "Default")
      (node (ref "5V") (pin "2") (pinfunction "2_2") (pintype "passive"))
      (node (ref "C1") (pin "1") (pinfunction "1_1") (pintype "passive"))
      (node (ref "C2") (pin "1") (pinfunction "P_1") (pintype "passive"))
      (node (ref "C3") (pin "2") (pinfunction "2_2") (pintype "passive"))
      (node (ref "J0") (pin "1") (pinfunction "1_1") (pintype "passive"))
      (node (ref "U3") (pin "3") (pinfunction "IN_3") (pintype "power_in"))
    )
    (net (code "49") (name "unconnected-(P1-GPIO0_8-Pad35)") (class "Default")
      (node (ref "P1") (pin "35") (pinfunction "GPIO0_8_35") (pintype "passive"))
    )
    (net (code "50") (name "unconnected-(P1-GPIO0_9-Pad33)") (class "Default")
      (node (ref "P1") (pin "33") (pinfunction "GPIO0_9_33") (pintype "passive"))
    )
    (net (code "51") (name "unconnected-(P1-GPIO0_10-Pad31)") (class "Default")
      (node (ref "P1") (pin "31") (pinfunction "GPIO0_10_31") (pintype "passive"))
    )
    (net (code "52") (name "unconnected-(P1-GPIO0_11-Pad32)") (class "Default")
      (node (ref "P1") (pin "32") (pinfunction "GPIO0_11_32") (pintype "passive"))
    )
    (net (code "53") (name "unconnected-(P1-GPIO1_0-Pad25)") (class "Default")
      (node (ref "P1") (pin "25") (pinfunction "GPIO1_0_25") (pintype "passive"))
    )
    (net (code "54") (name "unconnected-(P1-GPIO1_1-Pad24)") (class "Default")
      (node (ref "P1") (pin "24") (pinfunction "GPIO1_1_24") (pintype "passive"))
    )
    (net (code "55") (name "unconnected-(P1-GPIO1_4-Pad23)") (class "Default")
      (node (ref "P1") (pin "23") (pinfunction "GPIO1_4_23") (pintype "passive"))
    )
    (net (code "56") (name "unconnected-(P1-GPIO1_29-Pad26)") (class "Default")
      (node (ref "P1") (pin "26") (pinfunction "GPIO1_29_26") (pintype "passive"))
    )
    (net (code "57") (name "unconnected-(P1-GPIO2_6-Pad45)") (class "Default")
      (node (ref "P1") (pin "45") (pinfunction "GPIO2_6_45") (pintype "passive"))
    )
    (net (code "58") (name "unconnected-(P1-GPIO2_8-Pad43)") (class "Default")
      (node (ref "P1") (pin "43") (pinfunction "GPIO2_8_43") (pintype "passive"))
    )
    (net (code "59") (name "unconnected-(P1-GPIO2_9-Pad44)") (class "Default")
      (node (ref "P1") (pin "44") (pinfunction "GPIO2_9_44") (pintype "passive"))
    )
    (net (code "60") (name "unconnected-(P1-GPIO2_10-Pad41)") (class "Default")
      (node (ref "P1") (pin "41") (pinfunction "GPIO2_10_41") (pintype "passive"))
    )
    (net (code "61") (name "unconnected-(P1-GPIO2_11-Pad42)") (class "Default")
      (node (ref "P1") (pin "42") (pinfunction "GPIO2_11_42") (pintype "passive"))
    )
    (net (code "62") (name "unconnected-(P1-GPIO2_12-Pad39)") (class "Default")
      (node (ref "P1") (pin "39") (pinfunction "GPIO2_12_39") (pintype "passive"))
    )
    (net (code "63") (name "unconnected-(P1-GPIO2_13-Pad40)") (class "Default")
      (node (ref "P1") (pin "40") (pinfunction "GPIO2_13_40") (pintype "passive"))
    )
    (net (code "64") (name "unconnected-(P1-GPIO2_14{slash}S5_TX-Pad37)") (class "Default")
      (node (ref "P1") (pin "37") (pinfunction "GPIO2_14/S5_TX_37") (pintype "passive"))
    )
    (net (code "65") (name "unconnected-(P1-GPIO2_15{slash}S5_RX-Pad38)") (class "Default")
      (node (ref "P1") (pin "38") (pinfunction "GPIO2_15/S5_RX_38") (pintype "passive"))
    )
    (net (code "66") (name "unconnected-(P1-GPIO2_16-Pad36)") (class "Default")
      (node (ref "P1") (pin "36") (pinfunction "GPIO2_16_36") (pintype "passive"))
    )
    (net (code "67") (name "unconnected-(P1-GPIO2_17-Pad34)") (class "Default")
      (node (ref "P1") (pin "34") (pinfunction "GPIO2_17_34") (pintype "passive"))
    )
    (net (code "68") (name "unconnected-(P1-GPIO2_22-Pad27)") (class "Default")
      (node (ref "P1") (pin "27") (pinfunction "GPIO2_22_27") (pintype "passive"))
    )
    (net (code "69") (name "unconnected-(P1-GPIO2_23-Pad29)") (class "Default")
      (node (ref "P1") (pin "29") (pinfunction "GPIO2_23_29") (pintype "passive"))
    )
    (net (code "70") (name "unconnected-(P1-GPIO2_24-Pad28)") (class "Default")
      (node (ref "P1") (pin "28") (pinfunction "GPIO2_24_28") (pintype "passive"))
    )
    (net (code "71") (name "unconnected-(P1-GPIO2_25-Pad30)") (class "Default")
      (node (ref "P1") (pin "30") (pinfunction "GPIO2_25_30") (pintype "passive"))
    )
    (net (code "72") (name "unconnected-(P1-GPIO2_27-Pad46)") (class "Default")
      (node (ref "P1") (pin "46") (pinfunction "GPIO2_27_46") (pintype "passive"))
    )
    (net (code "73") (name "unconnected-(P2-AIN0-Pad39)") (class "Default")
      (node (ref "P2") (pin "39") (pinfunction "AIN0_39") (pintype "passive"))
    )
    (net (code "74") (name "unconnected-(P2-AIN3-Pad38)") (class "Default")
      (node (ref "P2") (pin "38") (pinfunction "AIN3_38") (pintype "passive"))
    )
    (net (code "75") (name "unconnected-(P2-AIN4-Pad33)") (class "Default")
      (node (ref "P2") (pin "33") (pinfunction "AIN4_33") (pintype "passive"))
    )
    (net (code "76") (name "unconnected-(P2-AIN5-Pad36)") (class "Default")
      (node (ref "P2") (pin "36") (pinfunction "AIN5_36") (pintype "passive"))
    )
    (net (code "77") (name "unconnected-(P2-AIN6-Pad35)") (class "Default")
      (node (ref "P2") (pin "35") (pinfunction "AIN6_35") (pintype "passive"))
    )
    (net (code "78") (name "unconnected-(P2-GND-Pad43)") (class "Default")
      (node (ref "P2") (pin "43") (pinfunction "GND_43") (pintype "passive"))
    )
    (net (code "79") (name "unconnected-(P2-GND-Pad45)") (class "Default")
      (node (ref "P2") (pin "45") (pinfunction "GND_45") (pintype "passive"))
    )
    (net (code "80") (name "unconnected-(P2-GND-Pad46)") (class "Default")
      (node (ref "P2") (pin "46") (pinfunction "GND_46") (pintype "passive"))
    )
    (net (code "81") (name "unconnected-(P2-GND_ADC-Pad34)") (class "Default")
      (node (ref "P2") (pin "34") (pinfunction "GND_ADC_34") (pintype "passive"))
    )
    (net (code "82") (name "unconnected-(P2-GPIO0_20-Pad41)") (class "Default")
      (node (ref "P2") (pin "41") (pinfunction "GPIO0_20_41") (pintype "passive"))
    )
    (net (code "83") (name "unconnected-(P2-GPIO3_14-Pad31)") (class "Default")
      (node (ref "P2") (pin "31") (pinfunction "GPIO3_14_31") (pintype "output"))
    )
    (net (code "84") (name "unconnected-(P2-GPIO3_15-Pad29)") (class "Default")
      (node (ref "P2") (pin "29") (pinfunction "GPIO3_15_29") (pintype "passive"))
    )
    (net (code "85") (name "unconnected-(P2-GPIO3_16-Pad30)") (class "Default")
      (node (ref "P2") (pin "30") (pinfunction "GPIO3_16_30") (pintype "passive"))
    )
    (net (code "86") (name "unconnected-(P2-GPIO3_17-Pad28)") (class "Default")
      (node (ref "P2") (pin "28") (pinfunction "GPIO3_17_28") (pintype "passive"))
    )
    (net (code "87") (name "unconnected-(P2-GPIO3_19-Pad27)") (class "Default")
      (node (ref "P2") (pin "27") (pinfunction "GPIO3_19_27") (pintype "passive"))
    )
    (net (code "88") (name "unconnected-(P2-VDD_ADC-Pad32)") (class "Default")
      (node (ref "P2") (pin "32") (pinfunction "VDD_ADC_32") (pintype "passive"))
    )
    (net (code "89") (name "unconnected-(U1C-FBKM-Pad9)") (class "Default")
      (node (ref "U1C") (pin "9") (pinfunction "FBKM_9") (pintype "input"))
    )
    (net (code "90") (name "unconnected-(U1C-FBKP-Pad12)") (class "Default")
      (node (ref "U1C") (pin "12") (pinfunction "FBKP_12") (pintype "input"))
    )
    (net (code "91") (name "unconnected-(U1C-INMD-Pad3)") (class "Default")
      (node (ref "U1C") (pin "3") (pinfunction "INMD_3") (pintype "passive"))
    )
    (net (code "92") (name "unconnected-(U1C-INPD-Pad2)") (class "Default")
      (node (ref "U1C") (pin "2") (pinfunction "INPD_2") (pintype "passive"))
    )
    (net (code "93") (name "unconnected-(U2-OSC-Pad7)") (class "Default")
      (node (ref "U2") (pin "7") (pinfunction "OSC_7") (pintype "input"))
    )
    (net (code "94") (name "unconnected-(U4-NC-Pad4)") (class "Default")
      (node (ref "U4") (pin "4") (pinfunction "NC_4") (pintype "input"))
    )
  )
)
